# Sheet1.net
KiCad netlist of a schematic drawn in Altium Designer
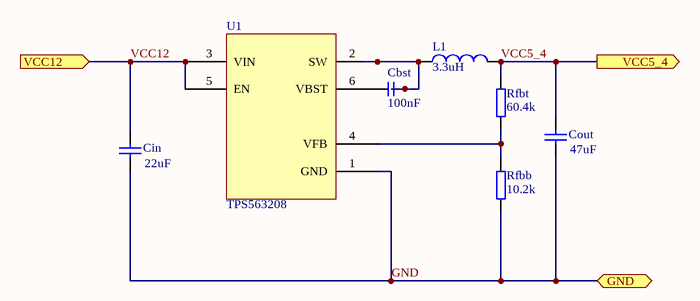
[diagram p0: Sheet1.SchDoc]

(export (version "E")
  (design (tool "Eeschema 10.0.6"))
  (components
    (comp (ref "Cbst")
      (value "100nF")
      (footprint "CAP0402R")
      (description "Capacitor")
      (libsource (lib "RevB2") (part "CAP"))
    )
    (comp (ref "Cin")
      (value "22uF")
      (footprint "RAD-0.3")
      (description "Capacitor")
      (fields (field (name "Comment") "Cap") (field (name "PUBLISHER") "Altium Limited"))
      (libsource (lib "Miscellaneous Devices") (part "Cap"))
    )
    (comp (ref "Cout")
      (value "47uF")
      (footprint "RAD-0.3")
      (description "Capacitor")
      (fields (field (name "Comment") "Cap") (field (name "PUBLISHER") "Altium Limited"))
      (libsource (lib "Miscellaneous Devices") (part "Cap"))
    )
    (comp (ref "L1")
      (value "3.3uH")
      (footprint "INDC4532")
      (description "Inductor")
      (fields (field (name "PUBLISHER") "Altium Limited"))
      (libsource (lib "Miscellaneous Devices") (part "Inductor"))
    )
    (comp (ref "Rfbb")
      (value "10.2k")
      (footprint "RES0402R")
      (description "Resistor")
      (libsource (lib "RevB2") (part "RES"))
    )
    (comp (ref "Rfbt")
      (value "60.4k")
      (footprint "RES0402R")
      (description "Resistor")
      (libsource (lib "RevB2") (part "RES"))
    )
    (comp (ref "U1") (value "TPS563208") (libsource (lib "PCB_Project1") (part "TPS563208")))
  )
  (nets
    (net (code "1") (name "/GND") (class "Default")
      (node (ref "Cin") (pin "1") (pinfunction "1_1") (pintype "passive"))
      (node (ref "Cout") (pin "1") (pinfunction "1_1") (pintype "passive"))
      (node (ref "Rfbb") (pin "1") (pinfunction "1_1") (pintype "passive"))
      (node (ref "U1") (pin "1") (pinfunction "GND_1") (pintype "passive"))
    )
    (net (code "2") (name "/VCC5_4") (class "Default")
      (node (ref "Cout") (pin "2") (pinfunction "2_2") (pintype "passive"))
      (node (ref "L1") (pin "2") (pinfunction "2_2") (pintype "passive"))
      (node (ref "Rfbt") (pin "2") (pinfunction "2_2") (pintype "passive"))
    )
    (net (code "3") (name "/VCC12") (class "Default")
      (node (ref "Cin") (pin "2") (pinfunction "2_2") (pintype "passive"))
      (node (ref "U1") (pin "3") (pinfunction "VIN_3") (pintype "passive"))
      (node (ref "U1") (pin "5") (pinfunction "EN_5") (pintype "passive"))
    )
    (net (code "4") (name "Net-(U1-SW)") (class "Default")
      (node (ref "Cbst") (pin "1") (pinfunction "1_1") (pintype "passive"))
      (node (ref "L1") (pin "1") (pinfunction "1_1") (pintype "passive"))
      (node (ref "U1") (pin "2") (pinfunction "SW_2") (pintype "passive"))
    )
    (net (code "5") (name "Net-(U1-VBST)") (class "Default")
      (node (ref "Cbst") (pin "2") (pinfunction "2_2") (pintype "passive"))
      (node (ref "U1") (pin "6") (pinfunction "VBST_6") (pintype "passive"))
    )
    (net (code "6") (name "Net-(U1-VFB)") (class "Default")
      (node (ref "Rfbb") (pin "2") (pinfunction "2_2") (pintype "passive"))
      (node (ref "Rfbt") (pin "1") (pinfunction "1_1") (pintype "passive"))
      (node (ref "U1") (pin "4") (pinfunction "VFB_4") (pintype "passive"))
    )
  )
)
